# French_USB_C.net
KiCad netlist of a schematic drawn in EAGLE
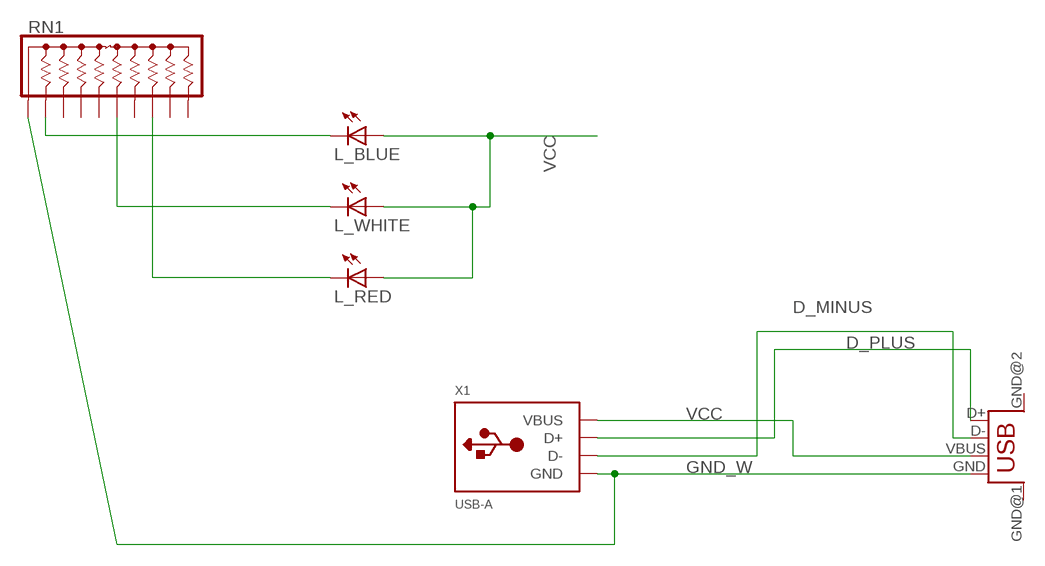
[diagram p0: schematic, sheet 1]

(export (version "E")
  (design (tool "Eeschema 10.0.6"))
  (components
    (comp (ref "L_BLUE")
      (value "LED5MM")
      (footprint "eagle-import:LED5MM")
      (libsource (lib "eagle-import") (part "LED5MM"))
    )
    (comp (ref "L_RED")
      (value "LED5MM")
      (footprint "eagle-import:LED5MM")
      (libsource (lib "eagle-import") (part "LED5MM"))
    )
    (comp (ref "L_WHITE")
      (value "LED5MM")
      (footprint "eagle-import:LED5MM")
      (libsource (lib "eagle-import") (part "LED5MM"))
    )
    (comp (ref "RN1")
      (value "4610X")
      (footprint "eagle-import:SIP10")
      (libsource (lib "eagle-import") (part "4610X"))
    )
    (comp (ref "U$1")
      (value "USB")
      (footprint "eagle-import:USB-FEMALE-A-PTH")
      (libsource (lib "eagle-import") (part "USB"))
    )
    (comp (ref "X1")
      (value "USB-A")
      (footprint "eagle-import:MOLEX_480371000")
      (libsource (lib "eagle-import") (part "USB-A"))
    )
  )
  (nets
    (net (code "1") (name "/D_MINUS") (class "Default")
      (node (ref "U$1") (pin "D-") (pinfunction "D-_D-") (pintype "bidirectional"))
      (node (ref "X1") (pin "2") (pinfunction "D-_2") (pintype "bidirectional"))
    )
    (net (code "2") (name "/D_PLUS") (class "Default")
      (node (ref "U$1") (pin "D+") (pinfunction "D+_D+") (pintype "bidirectional"))
      (node (ref "X1") (pin "3") (pinfunction "D+_3") (pintype "bidirectional"))
    )
    (net (code "3") (name "/GND_W") (class "Default")
      (node (ref "RN1") (pin "1") (pinfunction "1_1") (pintype "passive"))
      (node (ref "U$1") (pin "GND") (pinfunction "GND_GND") (pintype "bidirectional"))
      (node (ref "X1") (pin "4") (pinfunction "GND_4") (pintype "power_in"))
    )
    (net (code "4") (name "/VCC") (class "Default")
      (node (ref "L_BLUE") (pin "A") (pinfunction "A_A") (pintype "passive"))
      (node (ref "L_RED") (pin "A") (pinfunction "A_A") (pintype "passive"))
      (node (ref "L_WHITE") (pin "A") (pinfunction "A_A") (pintype "passive"))
      (node (ref "U$1") (pin "VBUS") (pinfunction "VBUS_VBUS") (pintype "bidirectional"))
      (node (ref "X1") (pin "1") (pinfunction "VBUS_1") (pintype "power_in"))
    )
    (net (code "5") (name "Net-(L_BLUE-C)") (class "Default")
      (node (ref "L_BLUE") (pin "K") (pinfunction "C_K") (pintype "passive"))
      (node (ref "RN1") (pin "2") (pinfunction "2_2") (pintype "passive"))
    )
    (net (code "6") (name "Net-(L_RED-C)") (class "Default")
      (node (ref "L_RED") (pin "K") (pinfunction "C_K") (pintype "passive"))
      (node (ref "RN1") (pin "8") (pinfunction "8_8") (pintype "passive"))
    )
    (net (code "7") (name "Net-(L_WHITE-C)") (class "Default")
      (node (ref "L_WHITE") (pin "K") (pinfunction "C_K") (pintype "passive"))
      (node (ref "RN1") (pin "6") (pinfunction "6_6") (pintype "passive"))
    )
    (net (code "8") (name "unconnected-(RN1-Pad3)") (class "Default")
      (node (ref "RN1") (pin "3") (pinfunction "3_3") (pintype "passive"))
    )
    (net (code "9") (name "unconnected-(RN1-Pad4)") (class "Default")
      (node (ref "RN1") (pin "4") (pinfunction "4_4") (pintype "passive"))
    )
    (net (code "10") (name "unconnected-(RN1-Pad5)") (class "Default")
      (node (ref "RN1") (pin "5") (pinfunction "5_5") (pintype "passive"))
    )
    (net (code "11") (name "unconnected-(RN1-Pad7)") (class "Default")
      (node (ref "RN1") (pin "7") (pinfunction "7_7") (pintype "passive"))
    )
    (net (code "12") (name "unconnected-(RN1-Pad9)") (class "Default")
      (node (ref "RN1") (pin "9") (pinfunction "9_9") (pintype "passive"))
    )
    (net (code "13") (name "unconnected-(RN1-Pad10)") (class "Default")
      (node (ref "RN1") (pin "10") (pinfunction "10_10") (pintype "passive"))
    )
    (net (code "14") (name "unconnected-(U$1-GND-PadGND@1)") (class "Default")
      (node (ref "U$1") (pin "GND@1") (pinfunction "GND_GND@1") (pintype "bidirectional"))
    )
    (net (code "15") (name "unconnected-(U$1-GND-PadGND@2)") (class "Default")
      (node (ref "U$1") (pin "GND@2") (pinfunction "GND_GND@2") (pintype "bidirectional"))
    )
  )
)
